# Debug.net
KiCad netlist of a schematic drawn in Altium Designer
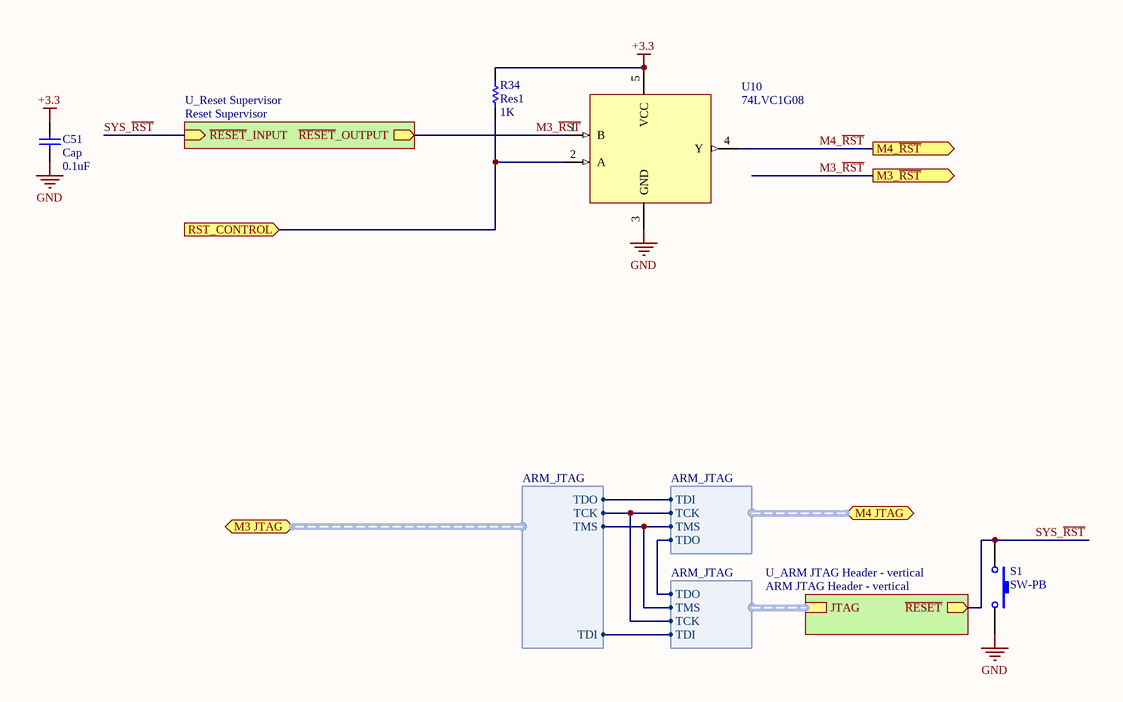
[diagram p0: Debug.SchDoc]

(export (version "E")
  (design (tool "Eeschema 10.0.6"))
  (components
    (comp (ref "C51")
      (value "Cap")
      (footprint "C0603")
      (description "Capacitor")
      (fields (field (name "ALTIUM_VALUE") "0.1uF") (field (name "PUBLISHER") "Altium Limited"))
      (libsource (lib "Miscellaneous Devices") (part "Cap"))
    )
    (comp (ref "R34")
      (value "Res1")
      (footprint "R0603")
      (description "Resistor")
      (fields (field (name "ALTIUM_VALUE") "1K") (field (name "PUBLISHER") "Altium Limited"))
      (libsource (lib "Miscellaneous Devices") (part "Res1"))
    )
    (comp (ref "S1")
      (value "SW-PB")
      (footprint "DTSM-32S-B")
      (description "Switch")
      (fields (field (name "PUBLISHER") "Altium Limited"))
      (libsource (lib "Miscellaneous Devices") (part "SW-PB"))
    )
    (comp (ref "U10")
      (value "74LVC1G08")
      (footprint "SOT23127P600-8N")
      (libsource (lib "74LVC1G08 (AND gate)") (part "74LVC1G08"))
    )
  )
  (nets
    (net (code "2") (name "+3.3") (class "Default")
      (node (ref "C51") (pin "1") (pinfunction "1_1") (pintype "passive"))
      (node (ref "R34") (pin "2") (pinfunction "2_2") (pintype "passive"))
      (node (ref "U10") (pin "5") (pinfunction "VCC_5") (pintype "power_in"))
    )
    (net (code "3") (name "/M3_~{RST}") (class "Default")
      (node (ref "U10") (pin "1") (pinfunction "B_1") (pintype "input"))
    )
    (net (code "4") (name "/M4_~{RST}") (class "Default")
      (node (ref "U10") (pin "4") (pinfunction "Y_4") (pintype "output"))
    )
    (net (code "5") (name "/RST_CONTROL") (class "Default")
      (node (ref "R34") (pin "1") (pinfunction "1_1") (pintype "passive"))
      (node (ref "U10") (pin "2") (pinfunction "A_2") (pintype "input"))
    )
    (net (code "6") (name "/SYS_~{RST}") (class "Default")
      (node (ref "S1") (pin "1") (pinfunction "1_1") (pintype "passive"))
    )
    (net (code "8") (name "GND") (class "Default")
      (node (ref "C51") (pin "2") (pinfunction "2_2") (pintype "passive"))
      (node (ref "S1") (pin "2") (pinfunction "2_2") (pintype "passive"))
      (node (ref "U10") (pin "3") (pinfunction "GND_3") (pintype "power_in"))
    )
  )
)
